# MODEM_PT2.net
KiCad netlist of a schematic drawn in Altium Designer
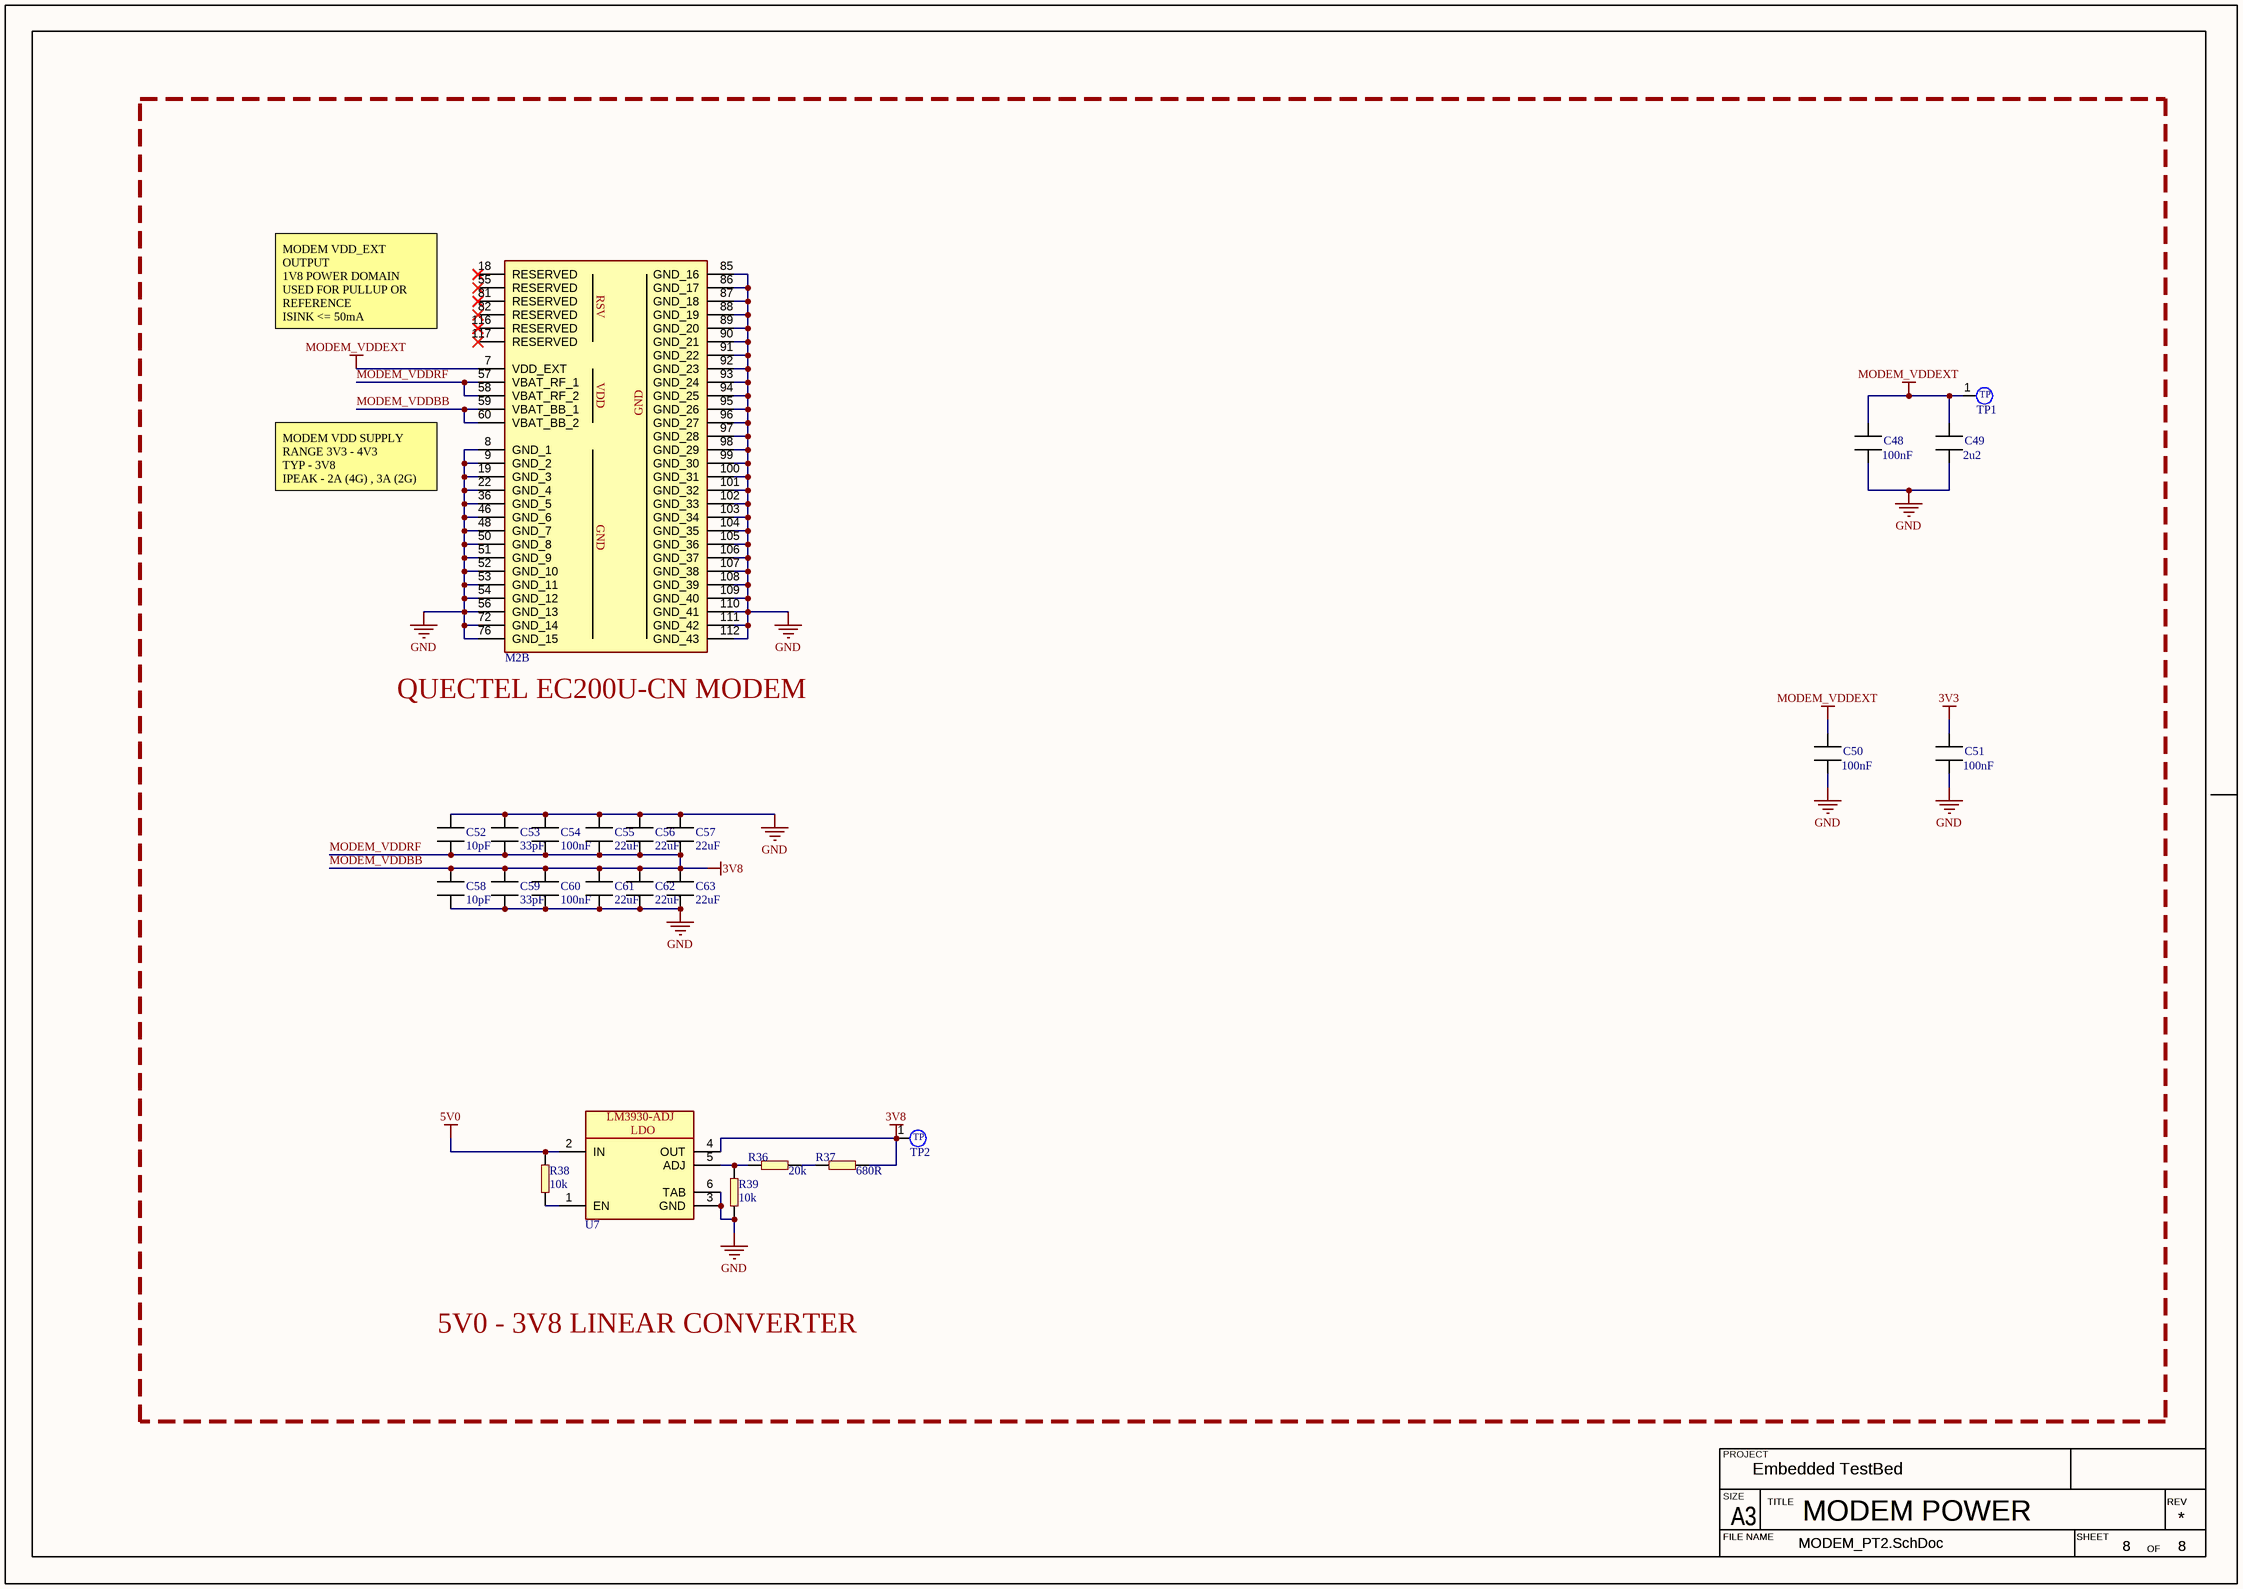
[diagram p0: MODEM_PT2.SchDoc]

(export (version "E")
  (design (tool "Eeschema 10.0.6"))
  (components
    (comp (ref "C48")
      (value "100nF")
      (footprint "CAPC2012X13L")
      (description "Chip Capacitor, 2-Leads, Body 2.00x1.25mm, IPC High Density")
      (fields (field (name "Comment") "MLCC_0805"))
      (libsource (lib "Capacitor") (part "MLCC_0805"))
    )
    (comp (ref "C49")
      (value "2u2")
      (footprint "CAPC2012X13L")
      (description "Chip Capacitor, 2-Leads, Body 2.00x1.25mm, IPC High Density")
      (fields (field (name "Comment") "MLCC_0805"))
      (libsource (lib "Capacitor") (part "MLCC_0805"))
    )
    (comp (ref "C50")
      (value "100nF")
      (footprint "CAPC2012X13L")
      (description "Chip Capacitor, 2-Leads, Body 2.00x1.25mm, IPC High Density")
      (fields (field (name "Comment") "MLCC_0805"))
      (libsource (lib "Capacitor") (part "MLCC_0805"))
    )
    (comp (ref "C51")
      (value "100nF")
      (footprint "CAPC2012X13L")
      (description "Chip Capacitor, 2-Leads, Body 2.00x1.25mm, IPC High Density")
      (fields (field (name "Comment") "MLCC_0805"))
      (libsource (lib "Capacitor") (part "MLCC_0805"))
    )
    (comp (ref "C52")
      (value "10pF")
      (footprint "CAPC2012X13L")
      (description "Chip Capacitor, 2-Leads, Body 2.00x1.25mm, IPC High Density")
      (fields (field (name "Comment") "MLCC_0805"))
      (libsource (lib "Capacitor") (part "MLCC_0805"))
    )
    (comp (ref "C53")
      (value "33pF")
      (footprint "CAPC2012X13L")
      (description "Chip Capacitor, 2-Leads, Body 2.00x1.25mm, IPC High Density")
      (fields (field (name "Comment") "MLCC_0805"))
      (libsource (lib "Capacitor") (part "MLCC_0805"))
    )
    (comp (ref "C54")
      (value "100nF")
      (footprint "CAPC2012X13L")
      (description "Chip Capacitor, 2-Leads, Body 2.00x1.25mm, IPC High Density")
      (fields (field (name "Comment") "MLCC_0805"))
      (libsource (lib "Capacitor") (part "MLCC_0805"))
    )
    (comp (ref "C55")
      (value "22uF")
      (footprint "CAPC2012X13L")
      (description "Chip Capacitor, 2-Leads, Body 2.00x1.25mm, IPC High Density")
      (fields (field (name "Comment") "MLCC_0805"))
      (libsource (lib "Capacitor") (part "MLCC_0805"))
    )
    (comp (ref "C56")
      (value "22uF")
      (footprint "CAPC2012X13L")
      (description "Chip Capacitor, 2-Leads, Body 2.00x1.25mm, IPC High Density")
      (fields (field (name "Comment") "MLCC_0805"))
      (libsource (lib "Capacitor") (part "MLCC_0805"))
    )
    (comp (ref "C57")
      (value "22uF")
      (footprint "CAPC2012X13L")
      (description "Chip Capacitor, 2-Leads, Body 2.00x1.25mm, IPC High Density")
      (fields (field (name "Comment") "MLCC_0805"))
      (libsource (lib "Capacitor") (part "MLCC_0805"))
    )
    (comp (ref "C58")
      (value "10pF")
      (footprint "CAPC2012X13L")
      (description "Chip Capacitor, 2-Leads, Body 2.00x1.25mm, IPC High Density")
      (fields (field (name "Comment") "MLCC_0805"))
      (libsource (lib "Capacitor") (part "MLCC_0805"))
    )
    (comp (ref "C59")
      (value "33pF")
      (footprint "CAPC2012X13L")
      (description "Chip Capacitor, 2-Leads, Body 2.00x1.25mm, IPC High Density")
      (fields (field (name "Comment") "MLCC_0805"))
      (libsource (lib "Capacitor") (part "MLCC_0805"))
    )
    (comp (ref "C60")
      (value "100nF")
      (footprint "CAPC2012X13L")
      (description "Chip Capacitor, 2-Leads, Body 2.00x1.25mm, IPC High Density")
      (fields (field (name "Comment") "MLCC_0805"))
      (libsource (lib "Capacitor") (part "MLCC_0805"))
    )
    (comp (ref "C61")
      (value "22uF")
      (footprint "CAPC2012X13L")
      (description "Chip Capacitor, 2-Leads, Body 2.00x1.25mm, IPC High Density")
      (fields (field (name "Comment") "MLCC_0805"))
      (libsource (lib "Capacitor") (part "MLCC_0805"))
    )
    (comp (ref "C62")
      (value "22uF")
      (footprint "CAPC2012X13L")
      (description "Chip Capacitor, 2-Leads, Body 2.00x1.25mm, IPC High Density")
      (fields (field (name "Comment") "MLCC_0805"))
      (libsource (lib "Capacitor") (part "MLCC_0805"))
    )
    (comp (ref "C63")
      (value "22uF")
      (footprint "CAPC2012X13L")
      (description "Chip Capacitor, 2-Leads, Body 2.00x1.25mm, IPC High Density")
      (fields (field (name "Comment") "MLCC_0805"))
      (libsource (lib "Capacitor") (part "MLCC_0805"))
    )
    (comp (ref "M2")
      (value "EC200U")
      (footprint "EC200U")
      (description "LTE CAT1 MODEM 144 SMD")
      (libsource (lib "WirelessModule") (part "EC200U"))
    )
    (comp (ref "R36")
      (value "20k")
      (footprint "RES_0603")
      (description "RES_0603")
      (fields (field (name "Comment") "ERP_101-1"))
      (libsource (lib "") (part "RES_0603_1"))
    )
    (comp (ref "R37")
      (value "680R")
      (footprint "RES_0603")
      (description "RES_0603")
      (fields (field (name "Comment") "ERP_101-1"))
      (libsource (lib "") (part "RES_0603_1"))
    )
    (comp (ref "R38")
      (value "10k")
      (footprint "RES_0603")
      (description "RES_0603")
      (fields (field (name "Comment") "ERP_101-1"))
      (libsource (lib "Resistor") (part "RES_0603"))
    )
    (comp (ref "R39")
      (value "10k")
      (footprint "RES_0603")
      (description "RES_0603")
      (fields (field (name "Comment") "ERP_101-1"))
      (libsource (lib "Resistor") (part "RES_0603"))
    )
    (comp (ref "TP1") (value "TP_1MM") (footprint "TP_1MM") (libsource (lib "Jumper") (part "TP_1MM")))
    (comp (ref "TP2") (value "TP_1MM") (footprint "TP_1MM") (libsource (lib "Jumper") (part "TP_1MM")))
    (comp (ref "U7")
      (value "LM39302")
      (footprint "DPAK170P1491X483-6N")
      (description "LM39302R HTC TO263 - Adjustable 3A Low-Voltage Low-Dropout Regulator")
      (libsource (lib "LinearRegulator") (part "LM39302"))
    )
  )
  (nets
    (net (code "1") (name "3V3") (class "Default")
      (node (ref "C51") (pin "1") (pinfunction "1_1") (pintype "passive"))
    )
    (net (code "2") (name "3V8") (class "Default")
      (node (ref "C52") (pin "2") (pinfunction "2_2") (pintype "passive"))
      (node (ref "C53") (pin "2") (pinfunction "2_2") (pintype "passive"))
      (node (ref "C54") (pin "2") (pinfunction "2_2") (pintype "passive"))
      (node (ref "C55") (pin "2") (pinfunction "2_2") (pintype "passive"))
      (node (ref "C56") (pin "2") (pinfunction "2_2") (pintype "passive"))
      (node (ref "C57") (pin "2") (pinfunction "2_2") (pintype "passive"))
      (node (ref "C58") (pin "1") (pinfunction "1_1") (pintype "passive"))
      (node (ref "C59") (pin "1") (pinfunction "1_1") (pintype "passive"))
      (node (ref "C60") (pin "1") (pinfunction "1_1") (pintype "passive"))
      (node (ref "C61") (pin "1") (pinfunction "1_1") (pintype "passive"))
      (node (ref "C62") (pin "1") (pinfunction "1_1") (pintype "passive"))
      (node (ref "C63") (pin "1") (pinfunction "1_1") (pintype "passive"))
      (node (ref "M2") (pin "57") (pinfunction "VBAT_RF_1_57") (pintype "passive"))
      (node (ref "M2") (pin "58") (pinfunction "VBAT_RF_2_58") (pintype "passive"))
      (node (ref "M2") (pin "59") (pinfunction "VBAT_BB_1_59") (pintype "passive"))
      (node (ref "M2") (pin "60") (pinfunction "VBAT_BB_2_60") (pintype "passive"))
      (node (ref "R37") (pin "1") (pinfunction "1_1") (pintype "passive"))
      (node (ref "TP2") (pin "1") (pinfunction "1_1") (pintype "passive"))
      (node (ref "U7") (pin "4") (pinfunction "OUT_4") (pintype "passive"))
    )
    (net (code "3") (name "5V0") (class "Default")
      (node (ref "R38") (pin "1") (pinfunction "1_1") (pintype "passive"))
      (node (ref "U7") (pin "2") (pinfunction "IN_2") (pintype "passive"))
    )
    (net (code "4") (name "GND") (class "Default")
      (node (ref "C48") (pin "2") (pinfunction "2_2") (pintype "passive"))
      (node (ref "C49") (pin "2") (pinfunction "2_2") (pintype "passive"))
      (node (ref "C50") (pin "2") (pinfunction "2_2") (pintype "passive"))
      (node (ref "C51") (pin "2") (pinfunction "2_2") (pintype "passive"))
      (node (ref "C52") (pin "1") (pinfunction "1_1") (pintype "passive"))
      (node (ref "C53") (pin "1") (pinfunction "1_1") (pintype "passive"))
      (node (ref "C54") (pin "1") (pinfunction "1_1") (pintype "passive"))
      (node (ref "C55") (pin "1") (pinfunction "1_1") (pintype "passive"))
      (node (ref "C56") (pin "1") (pinfunction "1_1") (pintype "passive"))
      (node (ref "C57") (pin "1") (pinfunction "1_1") (pintype "passive"))
      (node (ref "C58") (pin "2") (pinfunction "2_2") (pintype "passive"))
      (node (ref "C59") (pin "2") (pinfunction "2_2") (pintype "passive"))
      (node (ref "C60") (pin "2") (pinfunction "2_2") (pintype "passive"))
      (node (ref "C61") (pin "2") (pinfunction "2_2") (pintype "passive"))
      (node (ref "C62") (pin "2") (pinfunction "2_2") (pintype "passive"))
      (node (ref "C63") (pin "2") (pinfunction "2_2") (pintype "passive"))
      (node (ref "M2") (pin "100") (pinfunction "GND_31_100") (pintype "passive"))
      (node (ref "M2") (pin "101") (pinfunction "GND_32_101") (pintype "passive"))
      (node (ref "M2") (pin "102") (pinfunction "GND_33_102") (pintype "passive"))
      (node (ref "M2") (pin "103") (pinfunction "GND_34_103") (pintype "passive"))
      (node (ref "M2") (pin "104") (pinfunction "GND_35_104") (pintype "passive"))
      (node (ref "M2") (pin "105") (pinfunction "GND_36_105") (pintype "passive"))
      (node (ref "M2") (pin "106") (pinfunction "GND_37_106") (pintype "passive"))
      (node (ref "M2") (pin "107") (pinfunction "GND_38_107") (pintype "passive"))
      (node (ref "M2") (pin "108") (pinfunction "GND_39_108") (pintype "passive"))
      (node (ref "M2") (pin "109") (pinfunction "GND_40_109") (pintype "passive"))
      (node (ref "M2") (pin "110") (pinfunction "GND_41_110") (pintype "passive"))
      (node (ref "M2") (pin "111") (pinfunction "GND_42_111") (pintype "passive"))
      (node (ref "M2") (pin "112") (pinfunction "GND_43_112") (pintype "passive"))
      (node (ref "M2") (pin "19") (pinfunction "GND_3_19") (pintype "passive"))
      (node (ref "M2") (pin "22") (pinfunction "GND_4_22") (pintype "passive"))
      (node (ref "M2") (pin "36") (pinfunction "GND_5_36") (pintype "passive"))
      (node (ref "M2") (pin "46") (pinfunction "GND_6_46") (pintype "passive"))
      (node (ref "M2") (pin "48") (pinfunction "GND_7_48") (pintype "passive"))
      (node (ref "M2") (pin "50") (pinfunction "GND_8_50") (pintype "passive"))
      (node (ref "M2") (pin "51") (pinfunction "GND_9_51") (pintype "passive"))
      (node (ref "M2") (pin "52") (pinfunction "GND_10_52") (pintype "passive"))
      (node (ref "M2") (pin "53") (pinfunction "GND_11_53") (pintype "passive"))
      (node (ref "M2") (pin "54") (pinfunction "GND_12_54") (pintype "passive"))
      (node (ref "M2") (pin "56") (pinfunction "GND_13_56") (pintype "passive"))
      (node (ref "M2") (pin "72") (pinfunction "GND_14_72") (pintype "passive"))
      (node (ref "M2") (pin "76") (pinfunction "GND_15_76") (pintype "passive"))
      (node (ref "M2") (pin "8") (pinfunction "GND_1_8") (pintype "passive"))
      (node (ref "M2") (pin "85") (pinfunction "GND_16_85") (pintype "passive"))
      (node (ref "M2") (pin "86") (pinfunction "GND_17_86") (pintype "passive"))
      (node (ref "M2") (pin "87") (pinfunction "GND_18_87") (pintype "passive"))
      (node (ref "M2") (pin "88") (pinfunction "GND_19_88") (pintype "passive"))
      (node (ref "M2") (pin "89") (pinfunction "GND_20_89") (pintype "passive"))
      (node (ref "M2") (pin "9") (pinfunction "GND_2_9") (pintype "passive"))
      (node (ref "M2") (pin "90") (pinfunction "GND_21_90") (pintype "passive"))
      (node (ref "M2") (pin "91") (pinfunction "GND_22_91") (pintype "passive"))
      (node (ref "M2") (pin "92") (pinfunction "GND_23_92") (pintype "passive"))
      (node (ref "M2") (pin "93") (pinfunction "GND_24_93") (pintype "passive"))
      (node (ref "M2") (pin "94") (pinfunction "GND_25_94") (pintype "passive"))
      (node (ref "M2") (pin "95") (pinfunction "GND_26_95") (pintype "passive"))
      (node (ref "M2") (pin "96") (pinfunction "GND_27_96") (pintype "passive"))
      (node (ref "M2") (pin "97") (pinfunction "GND_28_97") (pintype "passive"))
      (node (ref "M2") (pin "98") (pinfunction "GND_29_98") (pintype "passive"))
      (node (ref "M2") (pin "99") (pinfunction "GND_30_99") (pintype "passive"))
      (node (ref "R39") (pin "2") (pinfunction "2_2") (pintype "passive"))
      (node (ref "U7") (pin "3") (pinfunction "GND_3") (pintype "passive"))
      (node (ref "U7") (pin "6") (pinfunction "TAB_6") (pintype "passive"))
    )
    (net (code "5") (name "MODEM_VDDEXT") (class "Default")
      (node (ref "C48") (pin "1") (pinfunction "1_1") (pintype "passive"))
      (node (ref "C49") (pin "1") (pinfunction "1_1") (pintype "passive"))
      (node (ref "C50") (pin "1") (pinfunction "1_1") (pintype "passive"))
      (node (ref "M2") (pin "7") (pinfunction "VDD_EXT_7") (pintype "passive"))
      (node (ref "TP1") (pin "1") (pinfunction "1_1") (pintype "passive"))
    )
    (net (code "6") (name "Net-(R36-Pad1)") (class "Default")
      (node (ref "R36") (pin "1") (pinfunction "1_1") (pintype "passive"))
      (node (ref "R37") (pin "2") (pinfunction "2_2") (pintype "passive"))
    )
    (net (code "7") (name "Net-(U7-ADJ)") (class "Default")
      (node (ref "R36") (pin "2") (pinfunction "2_2") (pintype "passive"))
      (node (ref "R39") (pin "1") (pinfunction "1_1") (pintype "passive"))
      (node (ref "U7") (pin "5") (pinfunction "ADJ_5") (pintype "passive"))
    )
    (net (code "8") (name "Net-(U7-EN)") (class "Default")
      (node (ref "R38") (pin "2") (pinfunction "2_2") (pintype "passive"))
      (node (ref "U7") (pin "1") (pinfunction "EN_1") (pintype "passive"))
    )
    (net (code "9") (name "unconnected-(M2B-RESERVED-Pad18)") (class "Default")
      (node (ref "M2") (pin "18") (pinfunction "RESERVED_18") (pintype "passive+no_connect"))
    )
    (net (code "10") (name "unconnected-(M2B-RESERVED-Pad55)") (class "Default")
      (node (ref "M2") (pin "55") (pinfunction "RESERVED_55") (pintype "passive+no_connect"))
    )
    (net (code "11") (name "unconnected-(M2B-RESERVED-Pad81)") (class "Default")
      (node (ref "M2") (pin "81") (pinfunction "RESERVED_81") (pintype "passive+no_connect"))
    )
    (net (code "12") (name "unconnected-(M2B-RESERVED-Pad82)") (class "Default")
      (node (ref "M2") (pin "82") (pinfunction "RESERVED_82") (pintype "passive+no_connect"))
    )
    (net (code "13") (name "unconnected-(M2B-RESERVED-Pad116)") (class "Default")
      (node (ref "M2") (pin "116") (pinfunction "RESERVED_116") (pintype "passive+no_connect"))
    )
    (net (code "14") (name "unconnected-(M2B-RESERVED-Pad117)") (class "Default")
      (node (ref "M2") (pin "117") (pinfunction "RESERVED_117") (pintype "passive+no_connect"))
    )
  )
)
